# robot.net
KiCad netlist of a schematic drawn in EAGLE
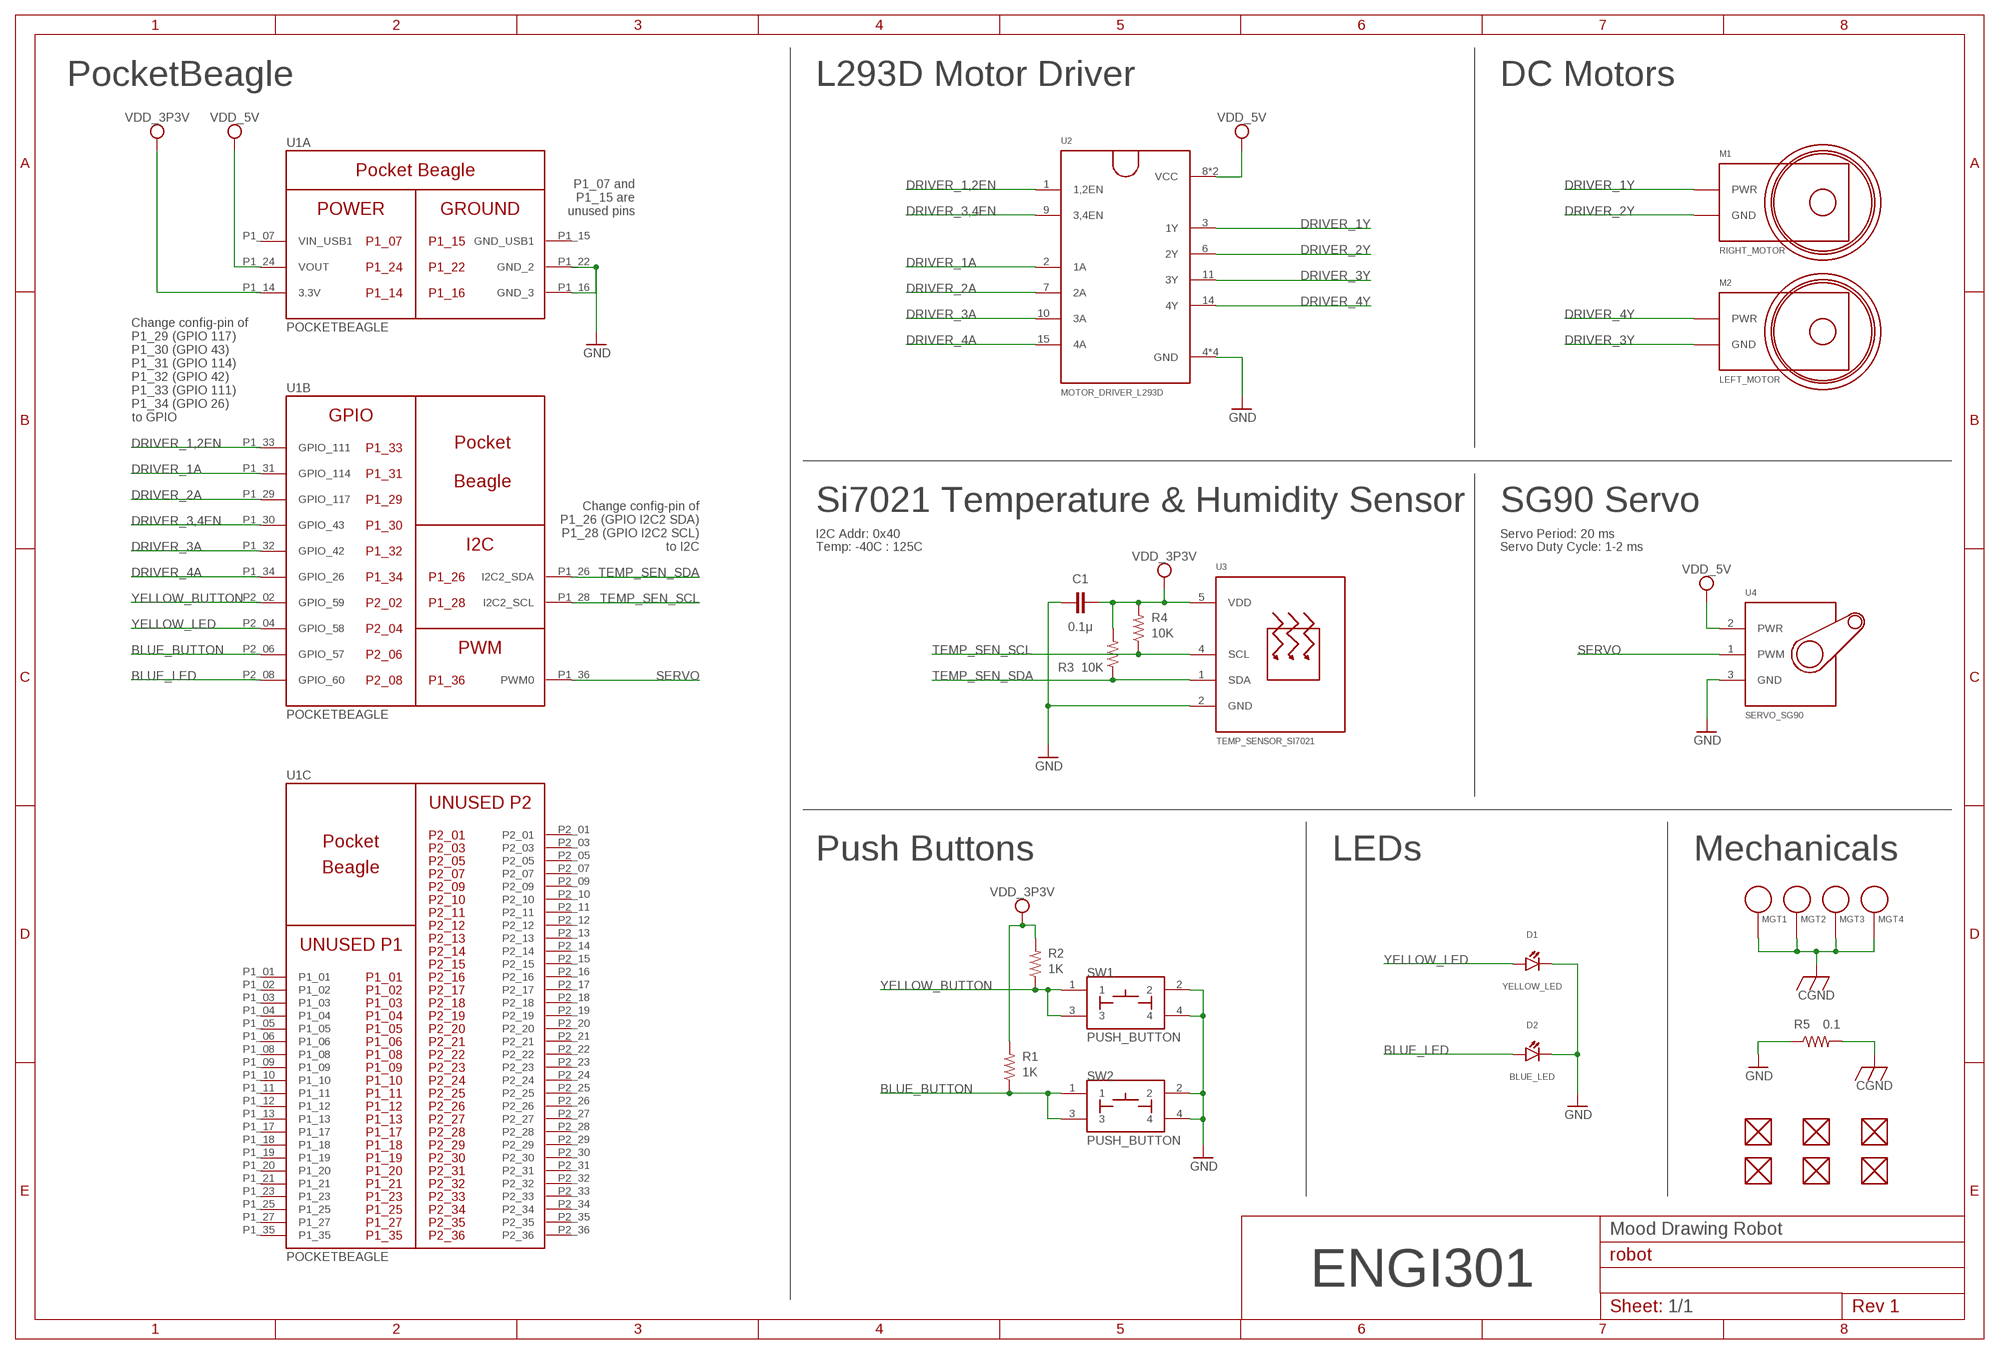
[diagram p0: schematic, sheet 1]

(export (version "E")
  (design (tool "Eeschema 10.0.6"))
  (components
    (comp (ref "C1")
      (value "0.1μ")
      (footprint "eagle-import:C0603")
      (libsource (lib "eagle-import") (part "C_C0603"))
    )
    (comp (ref "D1")
      (value "YELLOW_LED")
      (footprint "eagle-import:LED_EIA_STD")
      (libsource (lib "eagle-import") (part "LED"))
    )
    (comp (ref "D2")
      (value "BLUE_LED")
      (footprint "eagle-import:LED_EIA_STD")
      (libsource (lib "eagle-import") (part "LED"))
    )
    (comp (ref "FUD1")
      (value "FIDUCIAL")
      (footprint "eagle-import:FIDUCIAL_40MIL")
      (libsource (lib "eagle-import") (part "FIDUCIAL"))
    )
    (comp (ref "FUD2")
      (value "FIDUCIAL")
      (footprint "eagle-import:FIDUCIAL_40MIL")
      (libsource (lib "eagle-import") (part "FIDUCIAL"))
    )
    (comp (ref "FUD3")
      (value "FIDUCIAL")
      (footprint "eagle-import:FIDUCIAL_40MIL")
      (libsource (lib "eagle-import") (part "FIDUCIAL"))
    )
    (comp (ref "FUD4")
      (value "FIDUCIAL")
      (footprint "eagle-import:FIDUCIAL_40MIL")
      (libsource (lib "eagle-import") (part "FIDUCIAL"))
    )
    (comp (ref "FUD5")
      (value "FIDUCIAL")
      (footprint "eagle-import:FIDUCIAL_40MIL")
      (libsource (lib "eagle-import") (part "FIDUCIAL"))
    )
    (comp (ref "FUD6")
      (value "FIDUCIAL")
      (footprint "eagle-import:FIDUCIAL_40MIL")
      (libsource (lib "eagle-import") (part "FIDUCIAL"))
    )
    (comp (ref "M1")
      (value "RIGHT_MOTOR")
      (footprint "eagle-import:DC_MOTOR")
      (libsource (lib "eagle-import") (part "DC_MOTOR"))
    )
    (comp (ref "M2")
      (value "LEFT_MOTOR")
      (footprint "eagle-import:DC_MOTOR")
      (libsource (lib "eagle-import") (part "DC_MOTOR"))
    )
    (comp (ref "MGT1")
      (value "MOUNTING_HOLE")
      (footprint "eagle-import:MOUNTING_HOLE")
      (libsource (lib "eagle-import") (part "MOUNTING_HOLE"))
    )
    (comp (ref "MGT2")
      (value "MOUNTING_HOLE")
      (footprint "eagle-import:MOUNTING_HOLE")
      (libsource (lib "eagle-import") (part "MOUNTING_HOLE"))
    )
    (comp (ref "MGT3")
      (value "MOUNTING_HOLE")
      (footprint "eagle-import:MOUNTING_HOLE")
      (libsource (lib "eagle-import") (part "MOUNTING_HOLE"))
    )
    (comp (ref "MGT4")
      (value "MOUNTING_HOLE")
      (footprint "eagle-import:MOUNTING_HOLE")
      (libsource (lib "eagle-import") (part "MOUNTING_HOLE"))
    )
    (comp (ref "R1")
      (value "1K")
      (footprint "eagle-import:R0603")
      (libsource (lib "eagle-import") (part "R_R0603"))
    )
    (comp (ref "R2")
      (value "1K")
      (footprint "eagle-import:R0603")
      (libsource (lib "eagle-import") (part "R_R0603"))
    )
    (comp (ref "R3")
      (value "10K")
      (footprint "eagle-import:R0603")
      (libsource (lib "eagle-import") (part "R_R0603"))
    )
    (comp (ref "R4")
      (value "10K")
      (footprint "eagle-import:R0603")
      (libsource (lib "eagle-import") (part "R_R0603"))
    )
    (comp (ref "R5")
      (value "0.1")
      (footprint "eagle-import:R0805")
      (libsource (lib "eagle-import") (part "R_R0805"))
    )
    (comp (ref "SW1")
      (value "PUSH_BUTTON")
      (footprint "eagle-import:PUSH_BUTTON_12.5MM")
      (libsource (lib "eagle-import") (part "PUSH_BUTTON"))
    )
    (comp (ref "SW2")
      (value "PUSH_BUTTON")
      (footprint "eagle-import:PUSH_BUTTON_12.5MM")
      (libsource (lib "eagle-import") (part "PUSH_BUTTON"))
    )
    (comp (ref "U1")
      (value "POCKETBEAGLE")
      (footprint "eagle-import:POCKETBEAGLE")
      (libsource (lib "eagle-import") (part "POCKETBEAGLE"))
    )
    (comp (ref "U2")
      (value "MOTOR_DRIVER_L293D")
      (footprint "eagle-import:MOTOR_DRIVER")
      (libsource (lib "eagle-import") (part "MOTOR_DRIVER_L293D"))
    )
    (comp (ref "U3")
      (value "TEMP_SENSOR_SI7021")
      (footprint "eagle-import:TEMP_SENSOR")
      (libsource (lib "eagle-import") (part "TEMP_SENSOR_SI7021"))
    )
    (comp (ref "U4")
      (value "SERVO_SG90")
      (footprint "eagle-import:SERVO")
      (libsource (lib "eagle-import") (part "SERVO_SG90"))
    )
  )
  (nets
    (net (code "1") (name "/BLUE_BUTTON") (class "Default")
      (node (ref "R1") (pin "1") (pinfunction "1_1") (pintype "passive"))
      (node (ref "SW2") (pin "1") (pinfunction "1_1") (pintype "bidirectional"))
      (node (ref "SW2") (pin "3") (pinfunction "3_3") (pintype "bidirectional"))
      (node (ref "U1") (pin "P2_06") (pinfunction "GPIO_57_P2_06") (pintype "bidirectional"))
    )
    (net (code "2") (name "/BLUE_LED") (class "Default")
      (node (ref "D2") (pin "ANODE") (pinfunction "ANODE_ANODE") (pintype "bidirectional"))
      (node (ref "U1") (pin "P2_08") (pinfunction "GPIO_60_P2_08") (pintype "bidirectional"))
    )
    (net (code "3") (name "/DRIVER_1,2EN") (class "Default")
      (node (ref "U1") (pin "P1_33") (pinfunction "GPIO_111_P1_33") (pintype "bidirectional"))
      (node (ref "U2") (pin "1") (pinfunction "1,2EN_1") (pintype "bidirectional"))
    )
    (net (code "4") (name "/DRIVER_1A") (class "Default")
      (node (ref "U1") (pin "P1_31") (pinfunction "GPIO_114_P1_31") (pintype "bidirectional"))
      (node (ref "U2") (pin "2") (pinfunction "1A_2") (pintype "bidirectional"))
    )
    (net (code "5") (name "/DRIVER_1Y") (class "Default")
      (node (ref "M1") (pin "1") (pinfunction "PWR_1") (pintype "bidirectional"))
      (node (ref "U2") (pin "3") (pinfunction "1Y_3") (pintype "bidirectional"))
    )
    (net (code "6") (name "/DRIVER_2A") (class "Default")
      (node (ref "U1") (pin "P1_29") (pinfunction "GPIO_117_P1_29") (pintype "bidirectional"))
      (node (ref "U2") (pin "7") (pinfunction "2A_7") (pintype "bidirectional"))
    )
    (net (code "7") (name "/DRIVER_2Y") (class "Default")
      (node (ref "M1") (pin "2") (pinfunction "GND_2") (pintype "bidirectional"))
      (node (ref "U2") (pin "6") (pinfunction "2Y_6") (pintype "bidirectional"))
    )
    (net (code "8") (name "/DRIVER_3,4EN") (class "Default")
      (node (ref "U1") (pin "P1_30") (pinfunction "GPIO_43_P1_30") (pintype "bidirectional"))
      (node (ref "U2") (pin "9") (pinfunction "3,4EN_9") (pintype "bidirectional"))
    )
    (net (code "9") (name "/DRIVER_3A") (class "Default")
      (node (ref "U1") (pin "P1_32") (pinfunction "GPIO_42_P1_32") (pintype "bidirectional"))
      (node (ref "U2") (pin "10") (pinfunction "3A_10") (pintype "bidirectional"))
    )
    (net (code "10") (name "/DRIVER_3Y") (class "Default")
      (node (ref "M2") (pin "2") (pinfunction "GND_2") (pintype "bidirectional"))
      (node (ref "U2") (pin "11") (pinfunction "3Y_11") (pintype "bidirectional"))
    )
    (net (code "11") (name "/DRIVER_4A") (class "Default")
      (node (ref "U1") (pin "P1_34") (pinfunction "GPIO_26_P1_34") (pintype "bidirectional"))
      (node (ref "U2") (pin "15") (pinfunction "4A_15") (pintype "bidirectional"))
    )
    (net (code "12") (name "/DRIVER_4Y") (class "Default")
      (node (ref "M2") (pin "1") (pinfunction "PWR_1") (pintype "bidirectional"))
      (node (ref "U2") (pin "14") (pinfunction "4Y_14") (pintype "bidirectional"))
    )
    (net (code "13") (name "/SERVO") (class "Default")
      (node (ref "U1") (pin "P1_36") (pinfunction "PWM0_P1_36") (pintype "bidirectional"))
      (node (ref "U4") (pin "1") (pinfunction "PWM_1") (pintype "bidirectional"))
    )
    (net (code "14") (name "/TEMP_SEN_SCL") (class "Default")
      (node (ref "R4") (pin "1") (pinfunction "1_1") (pintype "passive"))
      (node (ref "U1") (pin "P1_28") (pinfunction "I2C2_SCL_P1_28") (pintype "bidirectional"))
      (node (ref "U3") (pin "4") (pinfunction "SCL_4") (pintype "bidirectional"))
    )
    (net (code "15") (name "/TEMP_SEN_SDA") (class "Default")
      (node (ref "R3") (pin "1") (pinfunction "1_1") (pintype "passive"))
      (node (ref "U1") (pin "P1_26") (pinfunction "I2C2_SDA_P1_26") (pintype "bidirectional"))
      (node (ref "U3") (pin "1") (pinfunction "SDA_1") (pintype "bidirectional"))
    )
    (net (code "16") (name "/VIN_USB1") (class "Default")
      (node (ref "U1") (pin "P1_07") (pinfunction "VIN_USB1_P1_07") (pintype "power_in"))
    )
    (net (code "17") (name "/YELLOW_BUTTON") (class "Default")
      (node (ref "R2") (pin "1") (pinfunction "1_1") (pintype "passive"))
      (node (ref "SW1") (pin "1") (pinfunction "1_1") (pintype "bidirectional"))
      (node (ref "SW1") (pin "3") (pinfunction "3_3") (pintype "bidirectional"))
      (node (ref "U1") (pin "P2_02") (pinfunction "GPIO_59_P2_02") (pintype "bidirectional"))
    )
    (net (code "18") (name "/YELLOW_LED") (class "Default")
      (node (ref "D1") (pin "ANODE") (pinfunction "ANODE_ANODE") (pintype "bidirectional"))
      (node (ref "U1") (pin "P2_04") (pinfunction "GPIO_58_P2_04") (pintype "bidirectional"))
    )
    (net (code "19") (name "CGND") (class "Default")
      (node (ref "MGT1") (pin "P$1") (pinfunction "P$1_P$1") (pintype "bidirectional"))
      (node (ref "MGT2") (pin "P$1") (pinfunction "P$1_P$1") (pintype "bidirectional"))
      (node (ref "MGT3") (pin "P$1") (pinfunction "P$1_P$1") (pintype "bidirectional"))
      (node (ref "MGT4") (pin "P$1") (pinfunction "P$1_P$1") (pintype "bidirectional"))
      (node (ref "R5") (pin "2") (pinfunction "2_2") (pintype "passive"))
    )
    (net (code "20") (name "GND") (class "Default")
      (node (ref "C1") (pin "1") (pinfunction "1_1") (pintype "passive"))
      (node (ref "D1") (pin "CATHODE") (pinfunction "CATHODE_CATHODE") (pintype "bidirectional"))
      (node (ref "D2") (pin "CATHODE") (pinfunction "CATHODE_CATHODE") (pintype "bidirectional"))
      (node (ref "R5") (pin "1") (pinfunction "1_1") (pintype "passive"))
      (node (ref "SW1") (pin "2") (pinfunction "2_2") (pintype "bidirectional"))
      (node (ref "SW1") (pin "4") (pinfunction "4_4") (pintype "bidirectional"))
      (node (ref "SW2") (pin "2") (pinfunction "2_2") (pintype "bidirectional"))
      (node (ref "SW2") (pin "4") (pinfunction "4_4") (pintype "bidirectional"))
      (node (ref "U1") (pin "P1_16") (pinfunction "GND_3_P1_16") (pintype "bidirectional"))
      (node (ref "U1") (pin "P1_22") (pinfunction "GND_2_P1_22") (pintype "bidirectional"))
      (node (ref "U2") (pin "12") (pinfunction "GND_12") (pintype "bidirectional"))
      (node (ref "U2") (pin "13") (pinfunction "GND_13") (pintype "bidirectional"))
      (node (ref "U2") (pin "4") (pinfunction "GND_4") (pintype "bidirectional"))
      (node (ref "U2") (pin "5") (pinfunction "GND_5") (pintype "bidirectional"))
      (node (ref "U3") (pin "2") (pinfunction "GND_2") (pintype "bidirectional"))
      (node (ref "U4") (pin "3") (pinfunction "GND_3") (pintype "bidirectional"))
    )
    (net (code "21") (name "VDD_3P3V") (class "Default")
      (node (ref "C1") (pin "2") (pinfunction "2_2") (pintype "passive"))
      (node (ref "R1") (pin "2") (pinfunction "2_2") (pintype "passive"))
      (node (ref "R2") (pin "2") (pinfunction "2_2") (pintype "passive"))
      (node (ref "R3") (pin "2") (pinfunction "2_2") (pintype "passive"))
      (node (ref "R4") (pin "2") (pinfunction "2_2") (pintype "passive"))
      (node (ref "U1") (pin "P1_14") (pinfunction "3.3V_P1_14") (pintype "power_in"))
      (node (ref "U3") (pin "5") (pinfunction "VDD_5") (pintype "power_in"))
    )
    (net (code "22") (name "VDD_5V") (class "Default")
      (node (ref "U1") (pin "P1_24") (pinfunction "VOUT_P1_24") (pintype "power_in"))
      (node (ref "U2") (pin "16") (pinfunction "VCC_16") (pintype "power_in"))
      (node (ref "U2") (pin "8") (pinfunction "VCC_8") (pintype "power_in"))
      (node (ref "U4") (pin "2") (pinfunction "PWR_2") (pintype "power_in"))
    )
    (net (code "23") (name "unconnected-(FUD1-PadP$1)") (class "Default")
      (node (ref "FUD1") (pin "P$1") (pinfunction "P$1_P$1") (pintype "no_connect"))
    )
    (net (code "24") (name "unconnected-(FUD2-PadP$1)") (class "Default")
      (node (ref "FUD2") (pin "P$1") (pinfunction "P$1_P$1") (pintype "no_connect"))
    )
    (net (code "25") (name "unconnected-(FUD3-PadP$1)") (class "Default")
      (node (ref "FUD3") (pin "P$1") (pinfunction "P$1_P$1") (pintype "no_connect"))
    )
    (net (code "26") (name "unconnected-(FUD4-PadP$1)") (class "Default")
      (node (ref "FUD4") (pin "P$1") (pinfunction "P$1_P$1") (pintype "no_connect"))
    )
    (net (code "27") (name "unconnected-(FUD5-PadP$1)") (class "Default")
      (node (ref "FUD5") (pin "P$1") (pinfunction "P$1_P$1") (pintype "no_connect"))
    )
    (net (code "28") (name "unconnected-(FUD6-PadP$1)") (class "Default")
      (node (ref "FUD6") (pin "P$1") (pinfunction "P$1_P$1") (pintype "no_connect"))
    )
    (net (code "29") (name "unconnected-(U1-PadP1_01)") (class "Default")
      (node (ref "U1") (pin "P1_01") (pinfunction "P1_01_P1_01") (pintype "bidirectional"))
    )
    (net (code "30") (name "unconnected-(U1-PadP1_02)") (class "Default")
      (node (ref "U1") (pin "P1_02") (pinfunction "P1_02_P1_02") (pintype "bidirectional"))
    )
    (net (code "31") (name "unconnected-(U1-PadP1_03)") (class "Default")
      (node (ref "U1") (pin "P1_03") (pinfunction "P1_03_P1_03") (pintype "bidirectional"))
    )
    (net (code "32") (name "unconnected-(U1-PadP1_04)") (class "Default")
      (node (ref "U1") (pin "P1_04") (pinfunction "P1_04_P1_04") (pintype "bidirectional"))
    )
    (net (code "33") (name "unconnected-(U1-PadP1_05)") (class "Default")
      (node (ref "U1") (pin "P1_05") (pinfunction "P1_05_P1_05") (pintype "bidirectional"))
    )
    (net (code "34") (name "unconnected-(U1-PadP1_06)") (class "Default")
      (node (ref "U1") (pin "P1_06") (pinfunction "P1_06_P1_06") (pintype "bidirectional"))
    )
    (net (code "35") (name "unconnected-(U1-PadP1_08)") (class "Default")
      (node (ref "U1") (pin "P1_08") (pinfunction "P1_08_P1_08") (pintype "bidirectional"))
    )
    (net (code "36") (name "unconnected-(U1-PadP1_09)") (class "Default")
      (node (ref "U1") (pin "P1_09") (pinfunction "P1_09_P1_09") (pintype "bidirectional"))
    )
    (net (code "37") (name "unconnected-(U1-PadP1_10)") (class "Default")
      (node (ref "U1") (pin "P1_10") (pinfunction "P1_10_P1_10") (pintype "bidirectional"))
    )
    (net (code "38") (name "unconnected-(U1-PadP1_11)") (class "Default")
      (node (ref "U1") (pin "P1_11") (pinfunction "P1_11_P1_11") (pintype "bidirectional"))
    )
    (net (code "39") (name "unconnected-(U1-PadP1_12)") (class "Default")
      (node (ref "U1") (pin "P1_12") (pinfunction "P1_12_P1_12") (pintype "bidirectional"))
    )
    (net (code "40") (name "unconnected-(U1-PadP1_13)") (class "Default")
      (node (ref "U1") (pin "P1_13") (pinfunction "P1_13_P1_13") (pintype "bidirectional"))
    )
    (net (code "41") (name "unconnected-(U1-PadP1_17)") (class "Default")
      (node (ref "U1") (pin "P1_17") (pinfunction "P1_17_P1_17") (pintype "bidirectional"))
    )
    (net (code "42") (name "unconnected-(U1-PadP1_18)") (class "Default")
      (node (ref "U1") (pin "P1_18") (pinfunction "P1_18_P1_18") (pintype "bidirectional"))
    )
    (net (code "43") (name "unconnected-(U1-PadP1_19)") (class "Default")
      (node (ref "U1") (pin "P1_19") (pinfunction "P1_19_P1_19") (pintype "bidirectional"))
    )
    (net (code "44") (name "unconnected-(U1-PadP1_20)") (class "Default")
      (node (ref "U1") (pin "P1_20") (pinfunction "P1_20_P1_20") (pintype "bidirectional"))
    )
    (net (code "45") (name "unconnected-(U1-PadP1_21)") (class "Default")
      (node (ref "U1") (pin "P1_21") (pinfunction "P1_21_P1_21") (pintype "bidirectional"))
    )
    (net (code "46") (name "unconnected-(U1-PadP1_23)") (class "Default")
      (node (ref "U1") (pin "P1_23") (pinfunction "P1_23_P1_23") (pintype "bidirectional"))
    )
    (net (code "47") (name "unconnected-(U1-PadP1_25)") (class "Default")
      (node (ref "U1") (pin "P1_25") (pinfunction "P1_25_P1_25") (pintype "bidirectional"))
    )
    (net (code "48") (name "unconnected-(U1-PadP1_27)") (class "Default")
      (node (ref "U1") (pin "P1_27") (pinfunction "P1_27_P1_27") (pintype "bidirectional"))
    )
    (net (code "49") (name "unconnected-(U1-PadP1_35)") (class "Default")
      (node (ref "U1") (pin "P1_35") (pinfunction "P1_35_P1_35") (pintype "bidirectional"))
    )
    (net (code "50") (name "unconnected-(U1-PadP2_01)") (class "Default")
      (node (ref "U1") (pin "P2_01") (pinfunction "P2_01_P2_01") (pintype "bidirectional"))
    )
    (net (code "51") (name "unconnected-(U1-PadP2_03)") (class "Default")
      (node (ref "U1") (pin "P2_03") (pinfunction "P2_03_P2_03") (pintype "bidirectional"))
    )
    (net (code "52") (name "unconnected-(U1-PadP2_05)") (class "Default")
      (node (ref "U1") (pin "P2_05") (pinfunction "P2_05_P2_05") (pintype "bidirectional"))
    )
    (net (code "53") (name "unconnected-(U1-PadP2_07)") (class "Default")
      (node (ref "U1") (pin "P2_07") (pinfunction "P2_07_P2_07") (pintype "bidirectional"))
    )
    (net (code "54") (name "unconnected-(U1-PadP2_09)") (class "Default")
      (node (ref "U1") (pin "P2_09") (pinfunction "P2_09_P2_09") (pintype "bidirectional"))
    )
    (net (code "55") (name "unconnected-(U1-PadP2_10)") (class "Default")
      (node (ref "U1") (pin "P2_10") (pinfunction "P2_10_P2_10") (pintype "bidirectional"))
    )
    (net (code "56") (name "unconnected-(U1-PadP2_11)") (class "Default")
      (node (ref "U1") (pin "P2_11") (pinfunction "P2_11_P2_11") (pintype "bidirectional"))
    )
    (net (code "57") (name "unconnected-(U1-PadP2_12)") (class "Default")
      (node (ref "U1") (pin "P2_12") (pinfunction "P2_12_P2_12") (pintype "bidirectional"))
    )
    (net (code "58") (name "unconnected-(U1-PadP2_13)") (class "Default")
      (node (ref "U1") (pin "P2_13") (pinfunction "P2_13_P2_13") (pintype "bidirectional"))
    )
    (net (code "59") (name "unconnected-(U1-PadP2_14)") (class "Default")
      (node (ref "U1") (pin "P2_14") (pinfunction "P2_14_P2_14") (pintype "bidirectional"))
    )
    (net (code "60") (name "unconnected-(U1-PadP2_15)") (class "Default")
      (node (ref "U1") (pin "P2_15") (pinfunction "P2_15_P2_15") (pintype "bidirectional"))
    )
    (net (code "61") (name "unconnected-(U1-PadP2_16)") (class "Default")
      (node (ref "U1") (pin "P2_16") (pinfunction "P2_16_P2_16") (pintype "bidirectional"))
    )
    (net (code "62") (name "unconnected-(U1-PadP2_17)") (class "Default")
      (node (ref "U1") (pin "P2_17") (pinfunction "P2_17_P2_17") (pintype "bidirectional"))
    )
    (net (code "63") (name "unconnected-(U1-PadP2_18)") (class "Default")
      (node (ref "U1") (pin "P2_18") (pinfunction "P2_18_P2_18") (pintype "bidirectional"))
    )
    (net (code "64") (name "unconnected-(U1-PadP2_19)") (class "Default")
      (node (ref "U1") (pin "P2_19") (pinfunction "P2_19_P2_19") (pintype "bidirectional"))
    )
    (net (code "65") (name "unconnected-(U1-PadP2_20)") (class "Default")
      (node (ref "U1") (pin "P2_20") (pinfunction "P2_20_P2_20") (pintype "bidirectional"))
    )
    (net (code "66") (name "unconnected-(U1-PadP2_21)") (class "Default")
      (node (ref "U1") (pin "P2_21") (pinfunction "P2_21_P2_21") (pintype "bidirectional"))
    )
    (net (code "67") (name "unconnected-(U1-PadP2_22)") (class "Default")
      (node (ref "U1") (pin "P2_22") (pinfunction "P2_22_P2_22") (pintype "bidirectional"))
    )
    (net (code "68") (name "unconnected-(U1-PadP2_23)") (class "Default")
      (node (ref "U1") (pin "P2_23") (pinfunction "P2_23_P2_23") (pintype "bidirectional"))
    )
    (net (code "69") (name "unconnected-(U1-PadP2_24)") (class "Default")
      (node (ref "U1") (pin "P2_24") (pinfunction "P2_24_P2_24") (pintype "bidirectional"))
    )
    (net (code "70") (name "unconnected-(U1-PadP2_25)") (class "Default")
      (node (ref "U1") (pin "P2_25") (pinfunction "P2_25_P2_25") (pintype "bidirectional"))
    )
    (net (code "71") (name "unconnected-(U1-PadP2_26)") (class "Default")
      (node (ref "U1") (pin "P2_26") (pinfunction "P2_26_P2_26") (pintype "bidirectional"))
    )
    (net (code "72") (name "unconnected-(U1-PadP2_27)") (class "Default")
      (node (ref "U1") (pin "P2_27") (pinfunction "P2_27_P2_27") (pintype "bidirectional"))
    )
    (net (code "73") (name "unconnected-(U1-PadP2_28)") (class "Default")
      (node (ref "U1") (pin "P2_28") (pinfunction "P2_28_P2_28") (pintype "bidirectional"))
    )
    (net (code "74") (name "unconnected-(U1-PadP2_29)") (class "Default")
      (node (ref "U1") (pin "P2_29") (pinfunction "P2_29_P2_29") (pintype "bidirectional"))
    )
    (net (code "75") (name "unconnected-(U1-PadP2_30)") (class "Default")
      (node (ref "U1") (pin "P2_30") (pinfunction "P2_30_P2_30") (pintype "bidirectional"))
    )
    (net (code "76") (name "unconnected-(U1-PadP2_31)") (class "Default")
      (node (ref "U1") (pin "P2_31") (pinfunction "P2_31_P2_31") (pintype "bidirectional"))
    )
    (net (code "77") (name "unconnected-(U1-PadP2_32)") (class "Default")
      (node (ref "U1") (pin "P2_32") (pinfunction "P2_32_P2_32") (pintype "bidirectional"))
    )
    (net (code "78") (name "unconnected-(U1-PadP2_33)") (class "Default")
      (node (ref "U1") (pin "P2_33") (pinfunction "P2_33_P2_33") (pintype "bidirectional"))
    )
    (net (code "79") (name "unconnected-(U1-PadP2_34)") (class "Default")
      (node (ref "U1") (pin "P2_34") (pinfunction "P2_34_P2_34") (pintype "bidirectional"))
    )
    (net (code "80") (name "unconnected-(U1-PadP2_35)") (class "Default")
      (node (ref "U1") (pin "P2_35") (pinfunction "P2_35_P2_35") (pintype "bidirectional"))
    )
    (net (code "81") (name "unconnected-(U1-PadP2_36)") (class "Default")
      (node (ref "U1") (pin "P2_36") (pinfunction "P2_36_P2_36") (pintype "bidirectional"))
    )
    (net (code "82") (name "unconnected-(U1A-GND_USB1-PadP1_15)") (class "Default")
      (node (ref "U1") (pin "P1_15") (pinfunction "GND_USB1_P1_15") (pintype "bidirectional"))
    )
  )
)
